# ProDocument___2024-03-31.net
KiCad netlist of a schematic drawn in EasyEDA Pro
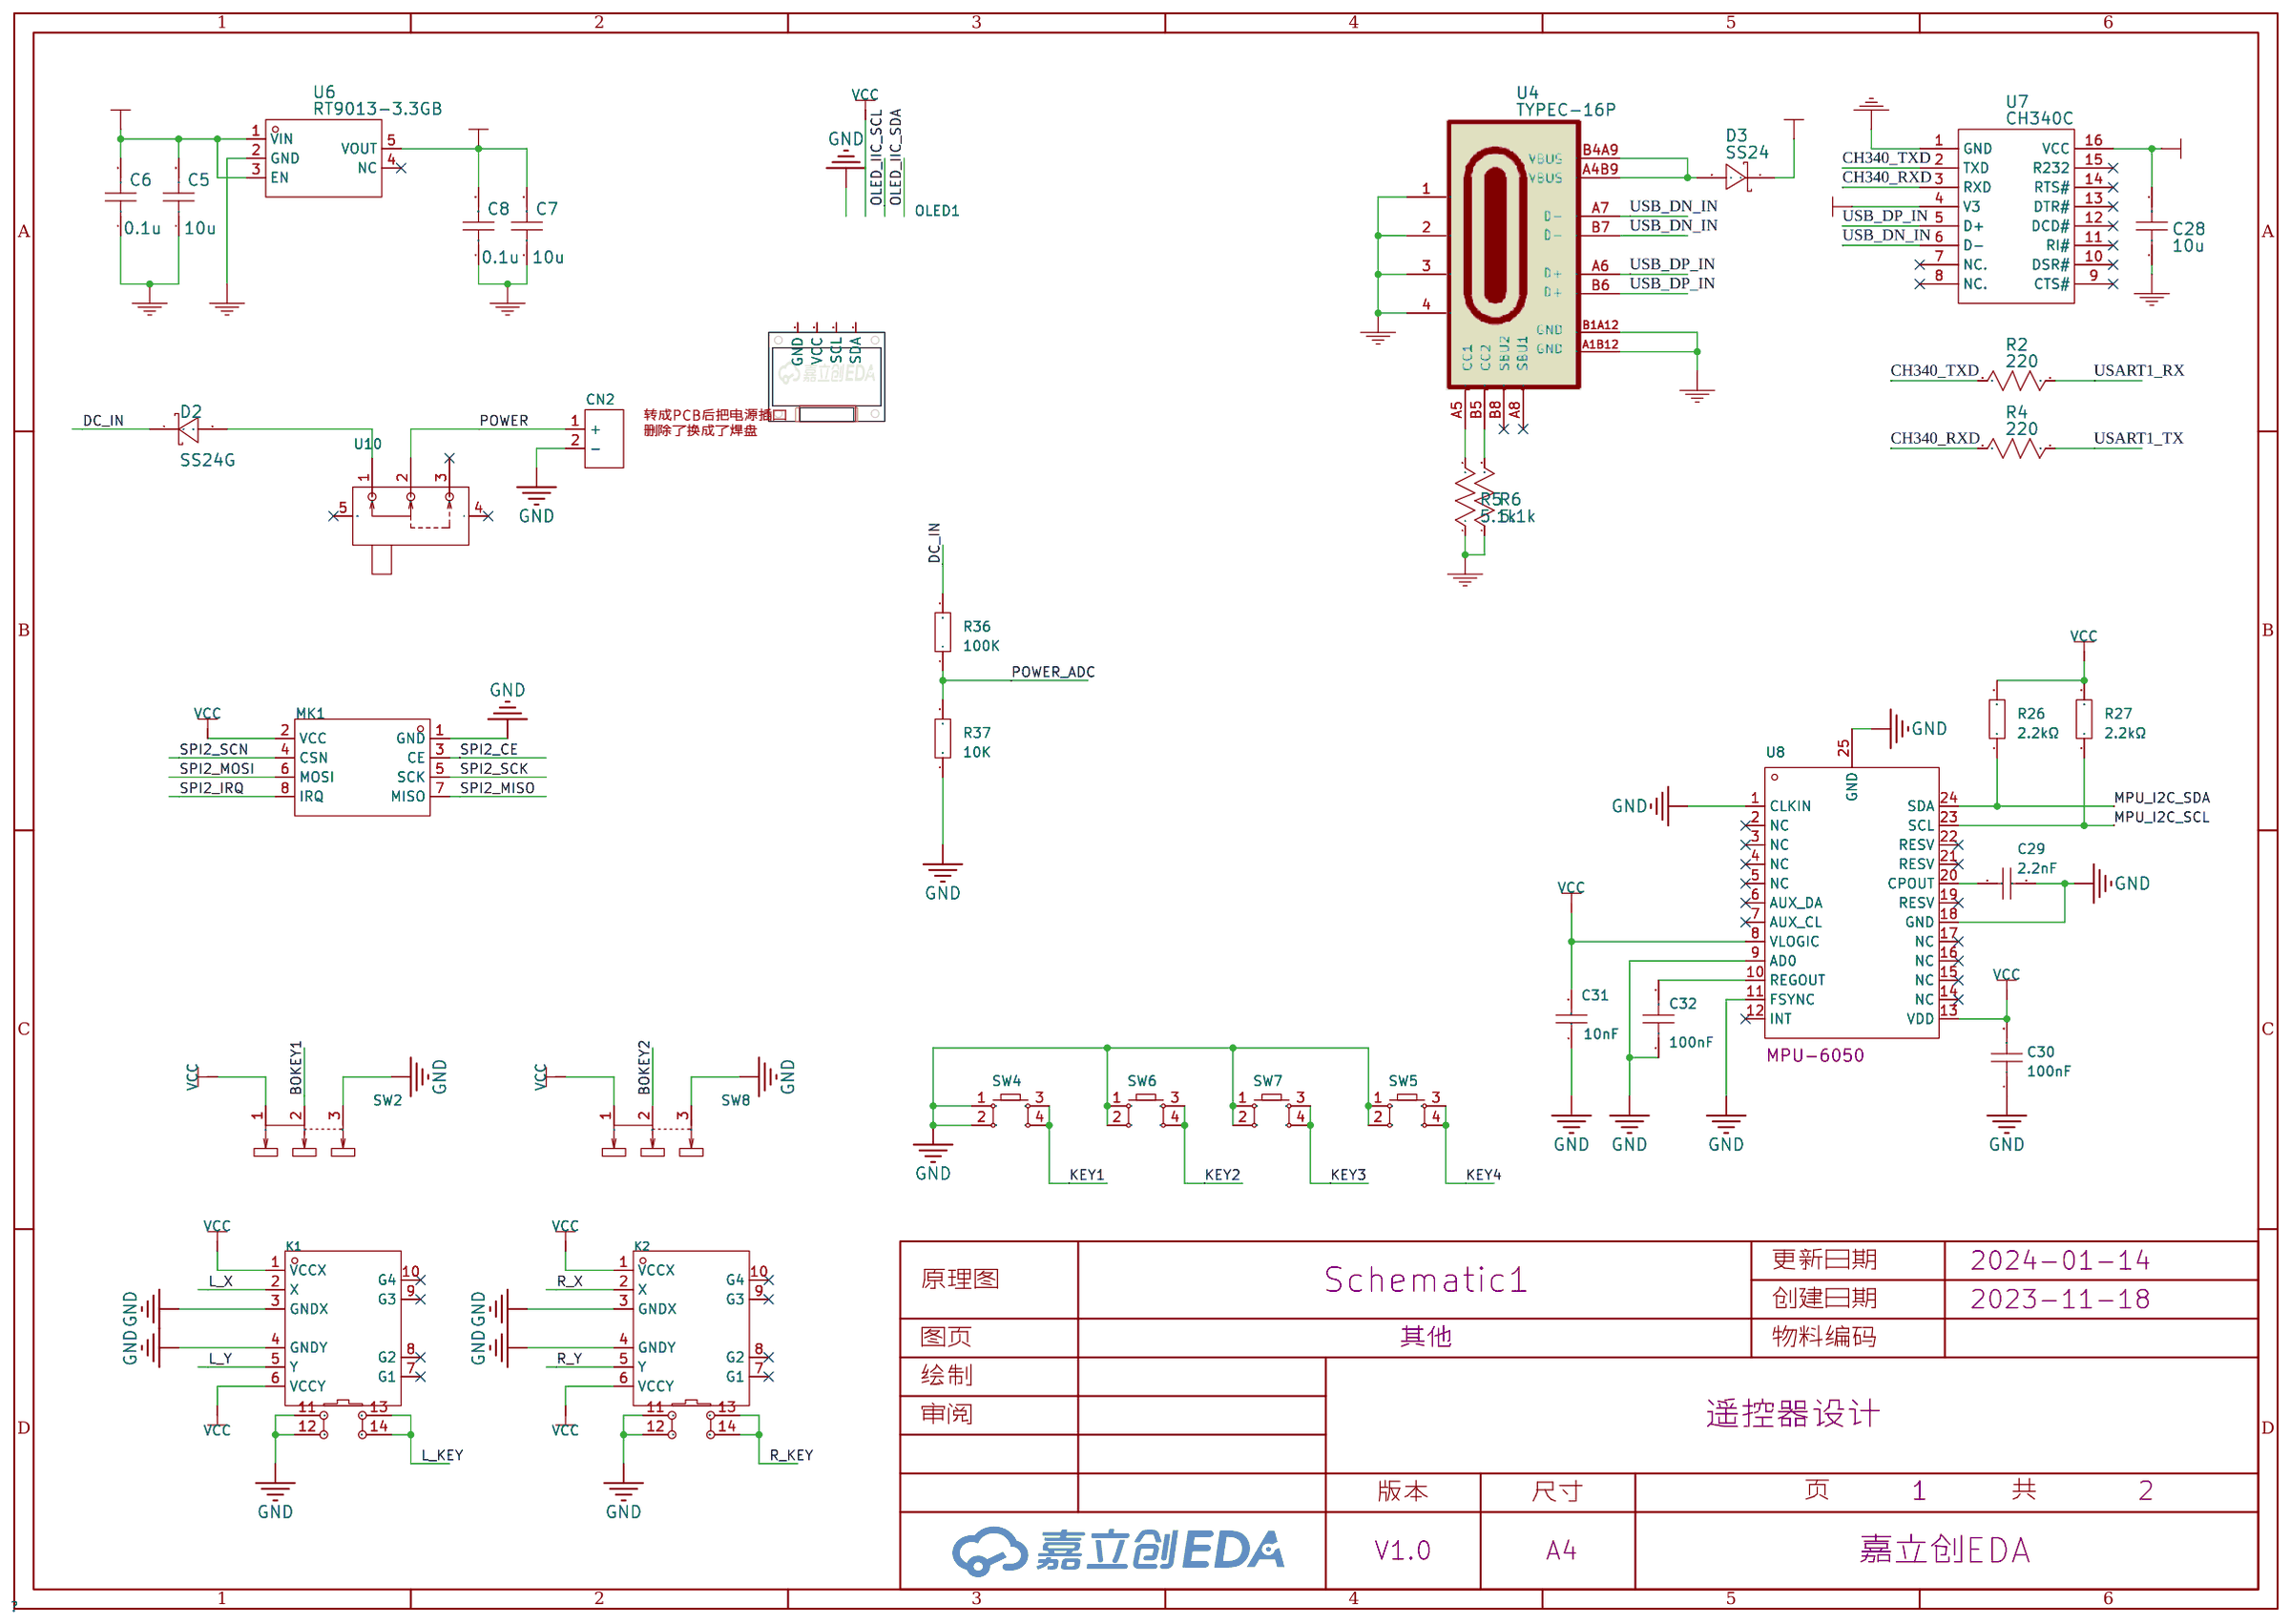
[diagram p0: 其他]
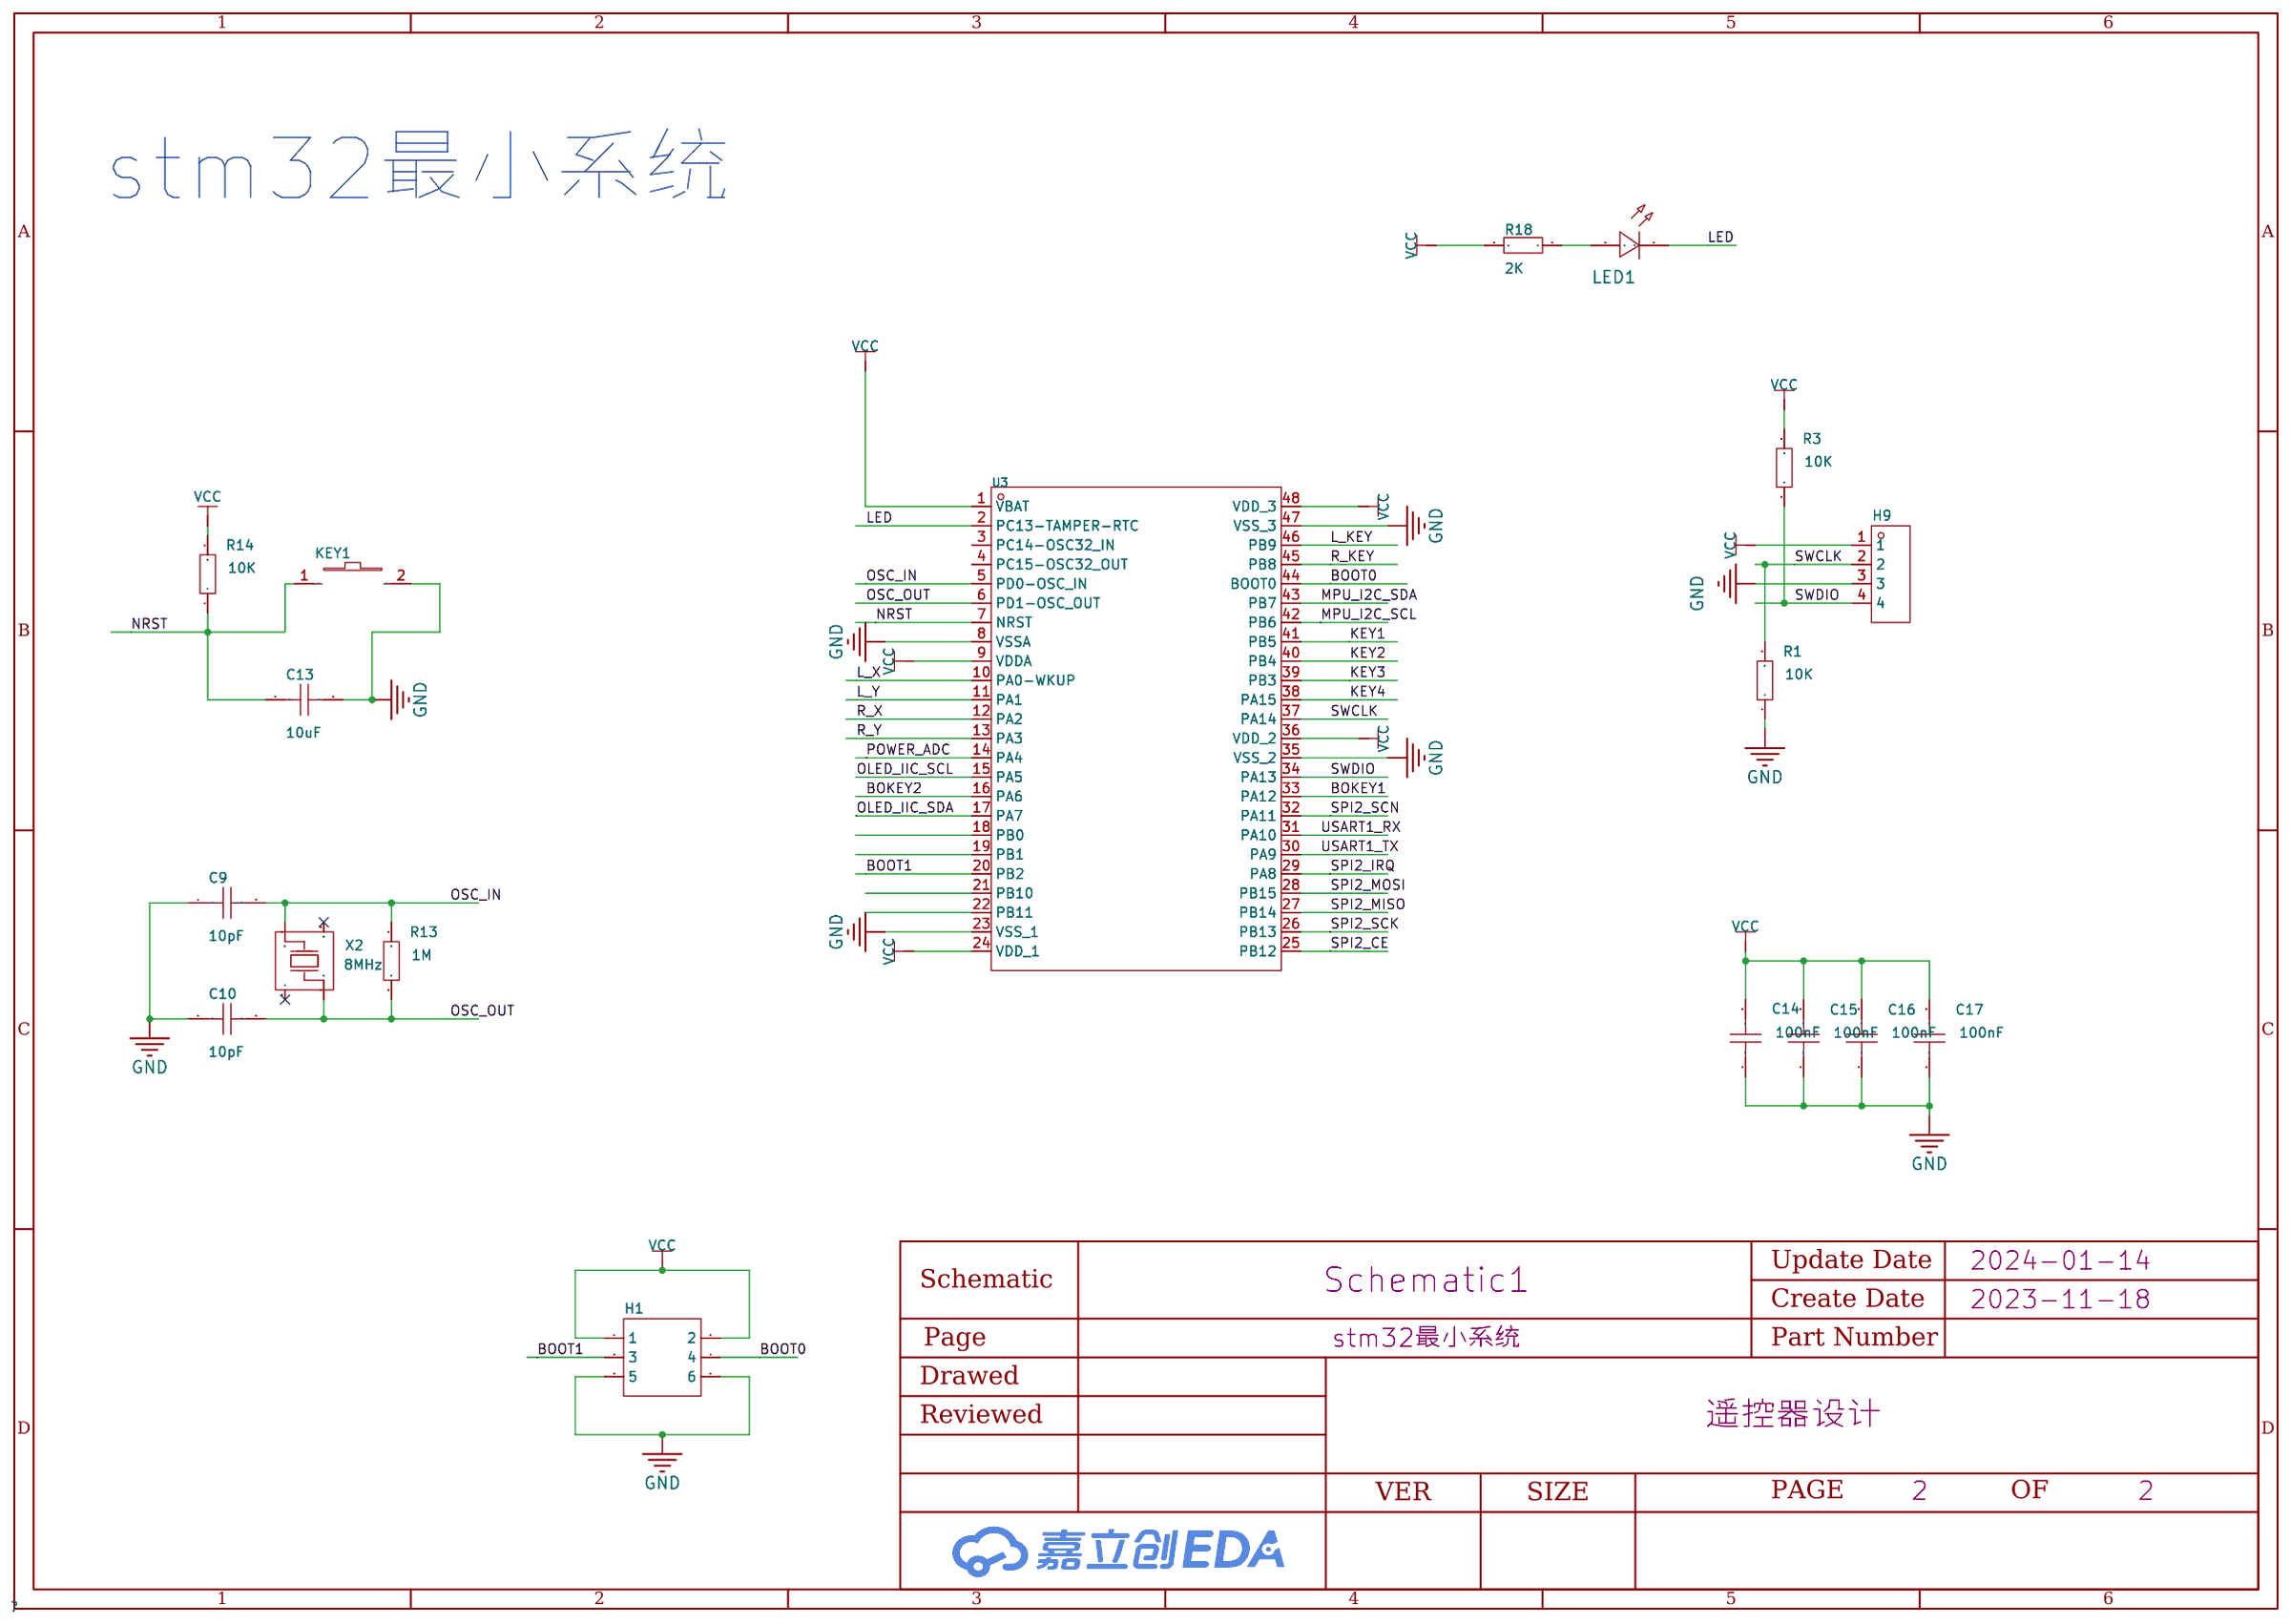
[diagram p1: stm32最小系统]

(export (version "E")
  (design (tool "Eeschema 10.0.6"))
  (components
    (comp (ref "C5") (value "10u") (footprint "easyedapro:C0603") (libsource (lib "easyedapro") (part "10u")))
    (comp (ref "C6")
      (value "0.1u")
      (footprint "easyedapro:C0603")
      (libsource (lib "easyedapro") (part "0.1u"))
    )
    (comp (ref "C7") (value "10u") (footprint "easyedapro:C0603") (libsource (lib "easyedapro") (part "10u")))
    (comp (ref "C8")
      (value "0.1u")
      (footprint "easyedapro:C0603")
      (libsource (lib "easyedapro") (part "0.1u"))
    )
    (comp (ref "C28")
      (value "10u")
      (footprint "easyedapro:C0603")
      (libsource (lib "easyedapro") (part "10u"))
    )
    (comp (ref "C29")
      (value "2.2nF")
      (footprint "easyedapro:C0402")
      (description "容值:2.2nF;精度:±10%;额定电压:50V;材质(温度系数):X7R;")
      (fields (field (name "Manufacturer Part") "0402B222K500NT") (field (name "Manufacturer") "FH(风华)"))
      (libsource (lib "easyedapro") (part "0402B222K500NT"))
    )
    (comp (ref "C30")
      (value "100nF")
      (footprint "easyedapro:C0402")
      (description "容值:100nF;精度:±10%;额定电压:16V;材质(温度系数):X7R;")
      (fields
        (field (name "Manufacturer Part") "CC0402KRX7R7BB104")
        (field (name "Manufacturer") "YAGEO(国巨)")
      )
      (libsource (lib "easyedapro") (part "CC0402KRX7R7BB104"))
    )
    (comp (ref "C31")
      (value "10nF")
      (footprint "easyedapro:C0402")
      (description "容值:10nF;精度:±10%;额定电压:50V;温度系数:X7R;")
      (fields
        (field (name "Manufacturer Part") "CC0402KRX7R9BB103")
        (field (name "Manufacturer") "YAGEO(国巨)")
      )
      (libsource (lib "easyedapro") (part "CC0402KRX7R9BB103"))
    )
    (comp (ref "C32")
      (value "100nF")
      (footprint "easyedapro:C0402")
      (description "容值:100nF;精度:±10%;额定电压:16V;材质(温度系数):X7R;")
      (fields
        (field (name "Manufacturer Part") "CC0402KRX7R7BB104")
        (field (name "Manufacturer") "YAGEO(国巨)")
      )
      (libsource (lib "easyedapro") (part "CC0402KRX7R7BB104"))
    )
    (comp (ref "CN2")
      (value "XT30UPB-F")
      (footprint "easyedapro:CONN-TH_XT30UPB-F")
      (description "模型插头连接器")
      (fields (field (name "Manufacturer") "AMASS(艾迈斯)"))
      (libsource (lib "easyedapro") (part "XT30UPB-F"))
    )
    (comp (ref "D2")
      (value "SS24G")
      (footprint "easyedapro:SMA_L4.4-W2.8-LS5.4-RD")
      (fields (field (name "Manufacturer") "SK"))
      (libsource (lib "easyedapro") (part "SS24G"))
    )
    (comp (ref "D3")
      (value "SS24")
      (footprint "easyedapro:SMA_L4.3-W2.6-LS5.2-RD")
      (fields (field (name "Manufacturer") "MDD"))
      (libsource (lib "easyedapro") (part "SS24"))
    )
    (comp (ref "K1")
      (value "~")
      (footprint "easyedapro:摇杆按键-16x16-直插")
      (libsource (lib "easyedapro") (part "摇杆-按键"))
    )
    (comp (ref "K2")
      (value "~")
      (footprint "easyedapro:摇杆按键-16x16-直插")
      (libsource (lib "easyedapro") (part "摇杆-按键"))
    )
    (comp (ref "MK1")
      (value "NF-04")
      (footprint "easyedapro:WIRELM-SMD_NRF24L01")
      (description "低成本NF-04台产芯片 功率加强版 最佳通讯距离240米，2.4G无线通讯模块")
      (fields (field (name "Manufacturer") "Ai-Thinker(安信可)"))
      (libsource (lib "easyedapro") (part "NRF24L01"))
    )
    (comp (ref "OLED1")
      (value "~")
      (footprint "easyedapro:0.96OLED_4P")
      (libsource (lib "easyedapro") (part "0.96OLED模块_4P"))
    )
    (comp (ref "R2") (value "220") (footprint "easyedapro:R0603") (libsource (lib "easyedapro") (part "220")))
    (comp (ref "R4") (value "220") (footprint "easyedapro:R0603") (libsource (lib "easyedapro") (part "220")))
    (comp (ref "R5")
      (value "5.1k")
      (footprint "easyedapro:R0603")
      (libsource (lib "easyedapro") (part "5.1k"))
    )
    (comp (ref "R6")
      (value "5.1k")
      (footprint "easyedapro:R0603")
      (libsource (lib "easyedapro") (part "5.1k"))
    )
    (comp (ref "R26")
      (value "2.2kΩ")
      (footprint "easyedapro:R0402")
      (description "电阻类型:厚膜电阻;阻值:2.2kΩ;精度:±1%;功率:62.5mW;温度系数:±100ppm/°C;最大工作电压:50V;工作温度范围:-55°C~+155°C;")
      (fields
        (field (name "Manufacturer Part") "0402WGF2201TCE")
        (field (name "Manufacturer") "UNI-ROYAL(厚声)")
      )
      (libsource (lib "easyedapro") (part "0402WGF2201TCE"))
    )
    (comp (ref "R27")
      (value "2.2kΩ")
      (footprint "easyedapro:R0402")
      (description "电阻类型:厚膜电阻;阻值:2.2kΩ;精度:±1%;功率:62.5mW;温度系数:±100ppm/°C;最大工作电压:50V;工作温度范围:-55°C~+155°C;")
      (fields
        (field (name "Manufacturer Part") "0402WGF2201TCE")
        (field (name "Manufacturer") "UNI-ROYAL(厚声)")
      )
      (libsource (lib "easyedapro") (part "0402WGF2201TCE"))
    )
    (comp (ref "R36")
      (value "100K")
      (footprint "easyedapro:R0603")
      (libsource (lib "easyedapro") (part "电阻"))
    )
    (comp (ref "R37") (value "10K") (footprint "easyedapro:R0603") (libsource (lib "easyedapro") (part "电阻")))
    (comp (ref "SW2")
      (value "SS-12D10L5")
      (footprint "easyedapro:SW-TH_SS-12D10L5")
      (description "额定电流(DC):3A;额定电压(DC):125V;额定电流(AC):3A;额定电压(AC):125V;电路结构:单刀双掷;安装方式:直插;机械寿命:1万次;开关颜色:黑色;")
      (fields (field (name "Manufacturer") "XKB Connectivity(中国星坤)"))
      (libsource (lib "easyedapro") (part "SS-12D10L5"))
    )
    (comp (ref "SW4")
      (value "~")
      (footprint "easyedapro:SW-TH_4P-L6.0-W6.0-P4.50-LS6.5")
      (libsource (lib "easyedapro") (part "轻触按键"))
    )
    (comp (ref "SW5")
      (value "~")
      (footprint "easyedapro:SW-TH_4P-L6.0-W6.0-P4.50-LS6.5")
      (libsource (lib "easyedapro") (part "轻触按键"))
    )
    (comp (ref "SW6")
      (value "~")
      (footprint "easyedapro:SW-TH_4P-L6.0-W6.0-P4.50-LS6.5")
      (libsource (lib "easyedapro") (part "轻触按键"))
    )
    (comp (ref "SW7")
      (value "~")
      (footprint "easyedapro:SW-TH_4P-L6.0-W6.0-P4.50-LS6.5")
      (libsource (lib "easyedapro") (part "轻触按键"))
    )
    (comp (ref "SW8")
      (value "SS-12D10L5")
      (footprint "easyedapro:SW-TH_SS-12D10L5")
      (description "额定电流(DC):3A;额定电压(DC):125V;额定电流(AC):3A;额定电压(AC):125V;电路结构:单刀双掷;安装方式:直插;机械寿命:1万次;开关颜色:黑色;")
      (fields (field (name "Manufacturer") "XKB Connectivity(中国星坤)"))
      (libsource (lib "easyedapro") (part "SS-12D10L5"))
    )
    (comp (ref "U4")
      (value "TYPEC-16P")
      (footprint "easyedapro:TYPEC")
      (libsource (lib "easyedapro") (part "TYPEC-16P"))
    )
    (comp (ref "U6")
      (value "RT9013-3.3GB")
      (footprint "easyedapro:SOT-23-5_L2.9-W1.6-P0.94-LS2.8-BL")
      (libsource (lib "easyedapro") (part "RT9013-3.3GB"))
    )
    (comp (ref "U7")
      (value "CH340C")
      (footprint "easyedapro:SOP-16_L10.0-W3.9-P1.27-LS6.0-BL")
      (fields (field (name "Manufacturer") "WCH(南京沁恒)"))
      (libsource (lib "easyedapro") (part "CH340C"))
    )
    (comp (ref "U8")
      (value "~")
      (footprint "easyedapro:QFN-24_L4.0-W4.0-P0.50-BL-EP2.7")
      (description "三轴加速度计和三轴陀螺仪，工作电压：2.375V~3.46V")
      (fields
        (field (name "Manufacturer Part") "MPU-6050")
        (field (name "Manufacturer") "TDK InvenSense(应美盛)")
      )
      (libsource (lib "easyedapro") (part "MPU-6050_C24112"))
    )
    (comp (ref "U10")
      (value "SS-12F23-G4")
      (footprint "easyedapro:SW-TH_SS-12F23-G040")
      (description "电路结构:单刀双掷;安装方式:卧插;开关颜色:黑色;滑钮形状:矩形柱状;引脚样式:PC引脚;开关长度:13mm;开关宽度:5.8mm;开关高度:9mm;")
      (fields (field (name "Manufacturer") "DEALON(德艺隆)"))
      (libsource (lib "easyedapro") (part "SS-12F23-G4"))
    )
    (comp (ref "C9")
      (value "10pF")
      (footprint "easyedapro:C0805")
      (libsource (lib "easyedapro") (part "C1210X7R475K630NT"))
    )
    (comp (ref "C10")
      (value "10pF")
      (footprint "easyedapro:C0805")
      (libsource (lib "easyedapro") (part "C1210X7R475K630NT"))
    )
    (comp (ref "C13")
      (value "10uF")
      (footprint "easyedapro:C0805")
      (fields
        (field (name "Manufacturer Part") "CC0603KRX7R9BB104")
        (field (name "Manufacturer") "YAGEO(国巨)")
        (field (name "Tolerance") "±10%")
      )
      (libsource (lib "easyedapro") (part "C1210X7R475K630NT"))
    )
    (comp (ref "C14")
      (value "100nF")
      (footprint "easyedapro:C0805")
      (libsource (lib "easyedapro") (part "C1210X7R475K630NT"))
    )
    (comp (ref "C15")
      (value "100nF")
      (footprint "easyedapro:C0805")
      (libsource (lib "easyedapro") (part "C1210X7R475K630NT"))
    )
    (comp (ref "C16")
      (value "100nF")
      (footprint "easyedapro:C0805")
      (libsource (lib "easyedapro") (part "C1210X7R475K630NT"))
    )
    (comp (ref "C17")
      (value "100nF")
      (footprint "easyedapro:C0805")
      (libsource (lib "easyedapro") (part "C1210X7R475K630NT"))
    )
    (comp (ref "H1")
      (value "~")
      (footprint "easyedapro:HDR-TH_6P-P2.54-V-F-R2-C3-S2.54")
      (libsource (lib "easyedapro") (part "HDR-F-2.54_2x3"))
    )
    (comp (ref "H9")
      (value "~")
      (footprint "easyedapro:HDR-TH_4P-P2.54-V-M")
      (libsource (lib "easyedapro") (part "PZ254V-11-04P"))
    )
    (comp (ref "KEY1")
      (value "轻触开关3x4x2")
      (footprint "easyedapro:SW-SMD_L4.0-W2.9-LS5.0")
      (description "触点电流:50mA;额定电压(DC):12V;电路结构:单刀单掷;安装方式:立贴;按钮形状:圆形按钮;带灯:-;开关长度:4mm;开关宽度:3mm;开关高度:2mm;")
      (fields (field (name "Manufacturer") "国产"))
      (libsource (lib "easyedapro") (part "Switch3x4x2"))
    )
    (comp (ref "LED1")
      (value "~")
      (footprint "easyedapro:LED0805-RD_RED")
      (libsource (lib "easyedapro") (part "LED_R"))
    )
    (comp (ref "R1") (value "10K") (footprint "easyedapro:R0603") (libsource (lib "easyedapro") (part "电阻")))
    (comp (ref "R3") (value "10K") (footprint "easyedapro:R0603") (libsource (lib "easyedapro") (part "电阻")))
    (comp (ref "R13") (value "1M") (footprint "easyedapro:R0603") (libsource (lib "easyedapro") (part "电阻")))
    (comp (ref "R14") (value "10K") (footprint "easyedapro:R0603") (libsource (lib "easyedapro") (part "电阻")))
    (comp (ref "R18") (value "2K") (footprint "easyedapro:R0603") (libsource (lib "easyedapro") (part "电阻")))
    (comp (ref "U3")
      (value "STM32F103C8T6")
      (footprint "easyedapro:LQFP-48_L7.0-W7.0-P0.50-LS9.0-BL")
      (fields (field (name "Manufacturer") "ST(意法半导体)"))
      (libsource (lib "easyedapro") (part "STM32F103C8T6"))
    )
    (comp (ref "X2")
      (value "8MHz")
      (footprint "easyedapro:OSC-SMD_4P-L3.2-W2.5-BL")
      (description "晶振类型:SMD 谐振器;频率:8MHz;频率公差:±10ppm;频率稳定度:±15ppm;负载电容:10pF;等效串联电阻(ESR):250Ω;工作温度:-;")
      (fields (field (name "Manufacturer Part") "TAXM8M4RDBCCT2T") (field (name "Manufacturer") "TAE(雅晶鑫)"))
      (libsource (lib "easyedapro") (part "TAXM8M4RDBCCT2T"))
    )
  )
  (nets
    (net (code "1") (name "BOKEY1") (class "Default")
      (node (ref "SW2") (pin "2") (pinfunction "2_2") (pintype "input"))
      (node (ref "U3") (pin "33") (pinfunction "PA12_33") (pintype "input"))
    )
    (net (code "2") (name "BOKEY2") (class "Default")
      (node (ref "SW8") (pin "2") (pinfunction "2_2") (pintype "input"))
      (node (ref "U3") (pin "16") (pinfunction "PA6_16") (pintype "input"))
    )
    (net (code "3") (name "BOOT0") (class "Default")
      (node (ref "H1") (pin "4") (pinfunction "4_4") (pintype "input"))
      (node (ref "U3") (pin "44") (pinfunction "BOOT0_44") (pintype "input"))
    )
    (net (code "4") (name "BOOT1") (class "Default")
      (node (ref "H1") (pin "3") (pinfunction "3_3") (pintype "input"))
      (node (ref "U3") (pin "20") (pinfunction "PB2_20") (pintype "input"))
    )
    (net (code "5") (name "CH340_RXD") (class "Default")
      (node (ref "R4") (pin "1") (pinfunction "1_1") (pintype "input"))
      (node (ref "U7") (pin "3") (pinfunction "RXD_3") (pintype "input"))
    )
    (net (code "6") (name "CH340_TXD") (class "Default")
      (node (ref "R2") (pin "1") (pinfunction "1_1") (pintype "input"))
      (node (ref "U7") (pin "2") (pinfunction "TXD_2") (pintype "input"))
    )
    (net (code "7") (name "DC_IN") (class "Default")
      (node (ref "C5") (pin "2") (pinfunction "2_2") (pintype "input"))
      (node (ref "C6") (pin "2") (pinfunction "2_2") (pintype "input"))
      (node (ref "D2") (pin "1") (pinfunction "1_1") (pintype "input"))
      (node (ref "D3") (pin "1") (pinfunction "K_1") (pintype "input"))
      (node (ref "R36") (pin "2") (pinfunction "2_2") (pintype "input"))
      (node (ref "U6") (pin "1") (pinfunction "VIN_1") (pintype "input"))
      (node (ref "U6") (pin "3") (pinfunction "EN_3") (pintype "input"))
    )
    (net (code "8") (name "GND") (class "Default")
      (node (ref "C10") (pin "1") (pinfunction "1_1") (pintype "input"))
      (node (ref "C13") (pin "2") (pinfunction "2_2") (pintype "input"))
      (node (ref "C14") (pin "1") (pinfunction "1_1") (pintype "input"))
      (node (ref "C15") (pin "1") (pinfunction "1_1") (pintype "input"))
      (node (ref "C16") (pin "1") (pinfunction "1_1") (pintype "input"))
      (node (ref "C17") (pin "1") (pinfunction "1_1") (pintype "input"))
      (node (ref "C28") (pin "1") (pinfunction "1_1") (pintype "input"))
      (node (ref "C29") (pin "2") (pinfunction "2_2") (pintype "input"))
      (node (ref "C30") (pin "1") (pinfunction "1_1") (pintype "input"))
      (node (ref "C31") (pin "1") (pinfunction "1_1") (pintype "input"))
      (node (ref "C32") (pin "1") (pinfunction "1_1") (pintype "input"))
      (node (ref "C5") (pin "1") (pinfunction "1_1") (pintype "input"))
      (node (ref "C6") (pin "1") (pinfunction "1_1") (pintype "input"))
      (node (ref "C7") (pin "1") (pinfunction "1_1") (pintype "input"))
      (node (ref "C8") (pin "1") (pinfunction "1_1") (pintype "input"))
      (node (ref "C9") (pin "1") (pinfunction "1_1") (pintype "input"))
      (node (ref "CN2") (pin "2") (pinfunction "-_2") (pintype "input"))
      (node (ref "H1") (pin "5") (pinfunction "5_5") (pintype "input"))
      (node (ref "H1") (pin "6") (pinfunction "6_6") (pintype "input"))
      (node (ref "H9") (pin "3") (pinfunction "3_3") (pintype "input"))
      (node (ref "K1") (pin "11") (pinfunction "10_11") (pintype "input"))
      (node (ref "K1") (pin "12") (pinfunction "11_12") (pintype "input"))
      (node (ref "K1") (pin "3") (pinfunction "GNDX_3") (pintype "input"))
      (node (ref "K1") (pin "4") (pinfunction "GNDY_4") (pintype "input"))
      (node (ref "K2") (pin "11") (pinfunction "10_11") (pintype "input"))
      (node (ref "K2") (pin "12") (pinfunction "11_12") (pintype "input"))
      (node (ref "K2") (pin "3") (pinfunction "GNDX_3") (pintype "input"))
      (node (ref "K2") (pin "4") (pinfunction "GNDY_4") (pintype "input"))
      (node (ref "KEY1") (pin "2") (pinfunction "2_2") (pintype "input"))
      (node (ref "MK1") (pin "1") (pinfunction "GND_1") (pintype "input"))
      (node (ref "R1") (pin "1") (pinfunction "1_1") (pintype "input"))
      (node (ref "R37") (pin "1") (pinfunction "1_1") (pintype "input"))
      (node (ref "R5") (pin "1") (pinfunction "1_1") (pintype "input"))
      (node (ref "R6") (pin "1") (pinfunction "1_1") (pintype "input"))
      (node (ref "SW2") (pin "3") (pinfunction "3_3") (pintype "input"))
      (node (ref "SW4") (pin "1") (pinfunction "1_1") (pintype "input"))
      (node (ref "SW4") (pin "2") (pinfunction "2_2") (pintype "input"))
      (node (ref "SW5") (pin "1") (pinfunction "1_1") (pintype "input"))
      (node (ref "SW5") (pin "2") (pinfunction "2_2") (pintype "input"))
      (node (ref "SW6") (pin "1") (pinfunction "1_1") (pintype "input"))
      (node (ref "SW6") (pin "2") (pinfunction "2_2") (pintype "input"))
      (node (ref "SW7") (pin "1") (pinfunction "1_1") (pintype "input"))
      (node (ref "SW7") (pin "2") (pinfunction "2_2") (pintype "input"))
      (node (ref "SW8") (pin "3") (pinfunction "3_3") (pintype "input"))
      (node (ref "U3") (pin "23") (pinfunction "VSS_1_23") (pintype "input"))
      (node (ref "U3") (pin "35") (pinfunction "VSS_2_35") (pintype "input"))
      (node (ref "U3") (pin "47") (pinfunction "VSS_3_47") (pintype "input"))
      (node (ref "U3") (pin "8") (pinfunction "VSSA_8") (pintype "input"))
      (node (ref "U4") (pin "1") (pinfunction "1_1") (pintype "input"))
      (node (ref "U4") (pin "2") (pinfunction "1_2") (pintype "input"))
      (node (ref "U4") (pin "3") (pinfunction "1_3") (pintype "input"))
      (node (ref "U4") (pin "4") (pinfunction "1_4") (pintype "input"))
      (node (ref "U4") (pin "A1B12") (pinfunction "1_A1B12") (pintype "input"))
      (node (ref "U4") (pin "B1A12") (pinfunction "1_B1A12") (pintype "input"))
      (node (ref "U6") (pin "2") (pinfunction "GND_2") (pintype "input"))
      (node (ref "U7") (pin "1") (pinfunction "GND_1") (pintype "input"))
      (node (ref "U8") (pin "1") (pinfunction "CLKIN_1") (pintype "input"))
      (node (ref "U8") (pin "11") (pinfunction "FSYNC_11") (pintype "input"))
      (node (ref "U8") (pin "18") (pinfunction "GND_18") (pintype "input"))
      (node (ref "U8") (pin "25") (pinfunction "GND_25") (pintype "input"))
      (node (ref "U8") (pin "9") (pinfunction "AD0_9") (pintype "input"))
    )
    (net (code "9") (name "KEY1") (class "Default")
      (node (ref "SW4") (pin "3") (pinfunction "3_3") (pintype "input"))
      (node (ref "SW4") (pin "4") (pinfunction "4_4") (pintype "input"))
      (node (ref "U3") (pin "41") (pinfunction "PB5_41") (pintype "input"))
    )
    (net (code "10") (name "KEY2") (class "Default")
      (node (ref "SW6") (pin "3") (pinfunction "3_3") (pintype "input"))
      (node (ref "SW6") (pin "4") (pinfunction "4_4") (pintype "input"))
      (node (ref "U3") (pin "40") (pinfunction "PB4_40") (pintype "input"))
    )
    (net (code "11") (name "KEY3") (class "Default")
      (node (ref "SW7") (pin "3") (pinfunction "3_3") (pintype "input"))
      (node (ref "SW7") (pin "4") (pinfunction "4_4") (pintype "input"))
      (node (ref "U3") (pin "39") (pinfunction "PB3_39") (pintype "input"))
    )
    (net (code "12") (name "KEY4") (class "Default")
      (node (ref "SW5") (pin "3") (pinfunction "3_3") (pintype "input"))
      (node (ref "SW5") (pin "4") (pinfunction "4_4") (pintype "input"))
      (node (ref "U3") (pin "38") (pinfunction "PA15_38") (pintype "input"))
    )
    (net (code "13") (name "LED") (class "Default")
      (node (ref "LED1") (pin "1") (pinfunction "C_1") (pintype "input"))
      (node (ref "U3") (pin "2") (pinfunction "PC13-TAMPER-RTC_2") (pintype "input"))
    )
    (net (code "14") (name "L_KEY") (class "Default")
      (node (ref "K1") (pin "13") (pinfunction "12_13") (pintype "input"))
      (node (ref "K1") (pin "14") (pinfunction "13_14") (pintype "input"))
      (node (ref "U3") (pin "46") (pinfunction "PB9_46") (pintype "input"))
    )
    (net (code "15") (name "L_X") (class "Default")
      (node (ref "K1") (pin "2") (pinfunction "X_2") (pintype "input"))
      (node (ref "U3") (pin "10") (pinfunction "PA0-WKUP_10") (pintype "input"))
    )
    (net (code "16") (name "L_Y") (class "Default")
      (node (ref "K1") (pin "5") (pinfunction "Y_5") (pintype "input"))
      (node (ref "U3") (pin "11") (pinfunction "PA1_11") (pintype "input"))
    )
    (net (code "17") (name "MPU_I2C_SCL") (class "Default")
      (node (ref "R27") (pin "1") (pinfunction "1_1") (pintype "input"))
      (node (ref "U3") (pin "42") (pinfunction "PB6_42") (pintype "input"))
      (node (ref "U8") (pin "23") (pinfunction "SCL_23") (pintype "input"))
    )
    (net (code "18") (name "MPU_I2C_SDA") (class "Default")
      (node (ref "R26") (pin "1") (pinfunction "1_1") (pintype "input"))
      (node (ref "U3") (pin "43") (pinfunction "PB7_43") (pintype "input"))
      (node (ref "U8") (pin "24") (pinfunction "SDA_24") (pintype "input"))
    )
    (net (code "19") (name "NRST") (class "Default")
      (node (ref "C13") (pin "1") (pinfunction "1_1") (pintype "input"))
      (node (ref "KEY1") (pin "1") (pinfunction "1_1") (pintype "input"))
      (node (ref "R14") (pin "1") (pinfunction "1_1") (pintype "input"))
      (node (ref "U3") (pin "7") (pinfunction "NRST_7") (pintype "input"))
    )
    (net (code "20") (name "Net-(D2-Pad2)") (class "Default")
      (node (ref "D2") (pin "2") (pinfunction "2_2") (pintype "input"))
      (node (ref "U10") (pin "1") (pinfunction "1_1") (pintype "input"))
    )
    (net (code "21") (name "Net-(D3-A)") (class "Default")
      (node (ref "D3") (pin "2") (pinfunction "A_2") (pintype "input"))
      (node (ref "U4") (pin "A4B9") (pinfunction "1_A4B9") (pintype "input"))
      (node (ref "U4") (pin "B4A9") (pinfunction "1_B4A9") (pintype "input"))
    )
    (net (code "22") (name "Net-(LED1-A)") (class "Default")
      (node (ref "LED1") (pin "2") (pinfunction "A_2") (pintype "input"))
      (node (ref "R18") (pin "1") (pinfunction "1_1") (pintype "input"))
    )
    (net (code "23") (name "Net-(R5-Pad2)") (class "Default")
      (node (ref "R5") (pin "2") (pinfunction "2_2") (pintype "input"))
      (node (ref "U4") (pin "A5") (pinfunction "1_A5") (pintype "input"))
    )
    (net (code "24") (name "Net-(R6-Pad2)") (class "Default")
      (node (ref "R6") (pin "2") (pinfunction "2_2") (pintype "input"))
      (node (ref "U4") (pin "B5") (pinfunction "1_B5") (pintype "input"))
    )
    (net (code "25") (name "Net-(U8-CPOUT)") (class "Default")
      (node (ref "C29") (pin "1") (pinfunction "1_1") (pintype "input"))
      (node (ref "U8") (pin "20") (pinfunction "CPOUT_20") (pintype "input"))
    )
    (net (code "26") (name "Net-(U8-REGOUT)") (class "Default")
      (node (ref "C32") (pin "2") (pinfunction "2_2") (pintype "input"))
      (node (ref "U8") (pin "10") (pinfunction "REGOUT_10") (pintype "input"))
    )
    (net (code "27") (name "OLED_IIC_SCL") (class "Default")
      (node (ref "U3") (pin "15") (pinfunction "PA5_15") (pintype "input"))
    )
    (net (code "28") (name "OLED_IIC_SDA") (class "Default")
      (node (ref "U3") (pin "17") (pinfunction "PA7_17") (pintype "input"))
    )
    (net (code "29") (name "OSC_IN") (class "Default")
      (node (ref "C9") (pin "2") (pinfunction "2_2") (pintype "input"))
      (node (ref "R13") (pin "2") (pinfunction "2_2") (pintype "input"))
      (node (ref "U3") (pin "5") (pinfunction "PD0-OSC_IN_5") (pintype "input"))
      (node (ref "X2") (pin "3") (pinfunction "3_3") (pintype "input"))
    )
    (net (code "30") (name "OSC_OUT") (class "Default")
      (node (ref "C10") (pin "2") (pinfunction "2_2") (pintype "input"))
      (node (ref "R13") (pin "1") (pinfunction "1_1") (pintype "input"))
      (node (ref "U3") (pin "6") (pinfunction "PD1-OSC_OUT_6") (pintype "input"))
      (node (ref "X2") (pin "1") (pinfunction "1_1") (pintype "input"))
    )
    (net (code "31") (name "POWER") (class "Default")
      (node (ref "CN2") (pin "1") (pinfunction "+_1") (pintype "input"))
      (node (ref "U10") (pin "2") (pinfunction "2_2") (pintype "input"))
    )
    (net (code "32") (name "POWER_ADC") (class "Default")
      (node (ref "R36") (pin "1") (pinfunction "1_1") (pintype "input"))
      (node (ref "R37") (pin "2") (pinfunction "2_2") (pintype "input"))
      (node (ref "U3") (pin "14") (pinfunction "PA4_14") (pintype "input"))
    )
    (net (code "33") (name "R_KEY") (class "Default")
      (node (ref "K2") (pin "13") (pinfunction "12_13") (pintype "input"))
      (node (ref "K2") (pin "14") (pinfunction "13_14") (pintype "input"))
      (node (ref "U3") (pin "45") (pinfunction "PB8_45") (pintype "input"))
    )
    (net (code "34") (name "R_X") (class "Default")
      (node (ref "K2") (pin "2") (pinfunction "X_2") (pintype "input"))
      (node (ref "U3") (pin "12") (pinfunction "PA2_12") (pintype "input"))
    )
    (net (code "35") (name "R_Y") (class "Default")
      (node (ref "K2") (pin "5") (pinfunction "Y_5") (pintype "input"))
      (node (ref "U3") (pin "13") (pinfunction "PA3_13") (pintype "input"))
    )
    (net (code "36") (name "SPI2_CE") (class "Default")
      (node (ref "MK1") (pin "3") (pinfunction "CE_3") (pintype "input"))
      (node (ref "U3") (pin "25") (pinfunction "PB12_25") (pintype "input"))
    )
    (net (code "37") (name "SPI2_IRQ") (class "Default")
      (node (ref "MK1") (pin "8") (pinfunction "IRQ_8") (pintype "input"))
      (node (ref "U3") (pin "29") (pinfunction "PA8_29") (pintype "input"))
    )
    (net (code "38") (name "SPI2_MISO") (class "Default")
      (node (ref "MK1") (pin "7") (pinfunction "MISO_7") (pintype "input"))
      (node (ref "U3") (pin "27") (pinfunction "PB14_27") (pintype "input"))
    )
    (net (code "39") (name "SPI2_MOSI") (class "Default")
      (node (ref "MK1") (pin "6") (pinfunction "MOSI_6") (pintype "input"))
      (node (ref "U3") (pin "28") (pinfunction "PB15_28") (pintype "input"))
    )
    (net (code "40") (name "SPI2_SCK") (class "Default")
      (node (ref "MK1") (pin "5") (pinfunction "SCK_5") (pintype "input"))
      (node (ref "U3") (pin "26") (pinfunction "PB13_26") (pintype "input"))
    )
    (net (code "41") (name "SPI2_SCN") (class "Default")
      (node (ref "MK1") (pin "4") (pinfunction "CSN_4") (pintype "input"))
      (node (ref "U3") (pin "32") (pinfunction "PA11_32") (pintype "input"))
    )
    (net (code "42") (name "SWCLK") (class "Default")
      (node (ref "H9") (pin "2") (pinfunction "2_2") (pintype "input"))
      (node (ref "R1") (pin "2") (pinfunction "2_2") (pintype "input"))
      (node (ref "U3") (pin "37") (pinfunction "PA14_37") (pintype "input"))
    )
    (net (code "43") (name "SWDIO") (class "Default")
      (node (ref "H9") (pin "4") (pinfunction "4_4") (pintype "input"))
      (node (ref "R3") (pin "1") (pinfunction "1_1") (pintype "input"))
      (node (ref "U3") (pin "34") (pinfunction "PA13_34") (pintype "input"))
    )
    (net (code "44") (name "USART1_RX") (class "Default")
      (node (ref "R2") (pin "2") (pinfunction "2_2") (pintype "input"))
      (node (ref "U3") (pin "31") (pinfunction "PA10_31") (pintype "input"))
    )
    (net (code "45") (name "USART1_TX") (class "Default")
      (node (ref "R4") (pin "2") (pinfunction "2_2") (pintype "input"))
      (node (ref "U3") (pin "30") (pinfunction "PA9_30") (pintype "input"))
    )
    (net (code "46") (name "USB_DN_IN") (class "Default")
      (node (ref "U4") (pin "A7") (pinfunction "1_A7") (pintype "input"))
      (node (ref "U4") (pin "B7") (pinfunction "1_B7") (pintype "input"))
      (node (ref "U7") (pin "6") (pinfunction "D-_6") (pintype "input"))
    )
    (net (code "47") (name "USB_DP_IN") (class "Default")
      (node (ref "U4") (pin "A6") (pinfunction "1_A6") (pintype "input"))
      (node (ref "U4") (pin "B6") (pinfunction "1_B6") (pintype "input"))
      (node (ref "U7") (pin "5") (pinfunction "D+_5") (pintype "input"))
    )
    (net (code "48") (name "VCC") (class "Default")
      (node (ref "C14") (pin "2") (pinfunction "2_2") (pintype "input"))
      (node (ref "C15") (pin "2") (pinfunction "2_2") (pintype "input"))
      (node (ref "C16") (pin "2") (pinfunction "2_2") (pintype "input"))
      (node (ref "C17") (pin "2") (pinfunction "2_2") (pintype "input"))
      (node (ref "C28") (pin "2") (pinfunction "2_2") (pintype "input"))
      (node (ref "C30") (pin "2") (pinfunction "2_2") (pintype "input"))
      (node (ref "C31") (pin "2") (pinfunction "2_2") (pintype "input"))
      (node (ref "C7") (pin "2") (pinfunction "2_2") (pintype "input"))
      (node (ref "C8") (pin "2") (pinfunction "2_2") (pintype "input"))
      (node (ref "H1") (pin "1") (pinfunction "1_1") (pintype "input"))
      (node (ref "H1") (pin "2") (pinfunction "2_2") (pintype "input"))
      (node (ref "H9") (pin "1") (pinfunction "1_1") (pintype "input"))
      (node (ref "K1") (pin "1") (pinfunction "VCCX_1") (pintype "input"))
      (node (ref "K1") (pin "6") (pinfunction "VCCY_6") (pintype "input"))
      (node (ref "K2") (pin "1") (pinfunction "VCCX_1") (pintype "input"))
      (node (ref "K2") (pin "6") (pinfunction "VCCY_6") (pintype "input"))
      (node (ref "MK1") (pin "2") (pinfunction "VCC_2") (pintype "input"))
      (node (ref "R14") (pin "2") (pinfunction "2_2") (pintype "input"))
      (node (ref "R18") (pin "2") (pinfunction "2_2") (pintype "input"))
      (node (ref "R26") (pin "2") (pinfunction "2_2") (pintype "input"))
      (node (ref "R27") (pin "2") (pinfunction "2_2") (pintype "input"))
      (node (ref "R3") (pin "2") (pinfunction "2_2") (pintype "input"))
      (node (ref "SW2") (pin "1") (pinfunction "1_1") (pintype "input"))
      (node (ref "SW8") (pin "1") (pinfunction "1_1") (pintype "input"))
      (node (ref "U3") (pin "1") (pinfunction "VBAT_1") (pintype "input"))
      (node (ref "U3") (pin "24") (pinfunction "VDD_1_24") (pintype "input"))
      (node (ref "U3") (pin "36") (pinfunction "VDD_2_36") (pintype "input"))
      (node (ref "U3") (pin "48") (pinfunction "VDD_3_48") (pintype "input"))
      (node (ref "U3") (pin "9") (pinfunction "VDDA_9") (pintype "input"))
      (node (ref "U6") (pin "5") (pinfunction "VOUT_5") (pintype "input"))
      (node (ref "U7") (pin "16") (pinfunction "VCC_16") (pintype "input"))
      (node (ref "U7") (pin "4") (pinfunction "V3_4") (pintype "input"))
      (node (ref "U8") (pin "13") (pinfunction "VDD_13") (pintype "input"))
      (node (ref "U8") (pin "8") (pinfunction "VLOGIC_8") (pintype "input"))
    )
    (net (code "49") (name "unconnected-(K1-G1-Pad7)") (class "Default")
      (node (ref "K1") (pin "7") (pinfunction "G1_7") (pintype "input+no_connect"))
    )
    (net (code "50") (name "unconnected-(K1-G2-Pad8)") (class "Default")
      (node (ref "K1") (pin "8") (pinfunction "G2_8") (pintype "input+no_connect"))
    )
    (net (code "51") (name "unconnected-(K1-G3-Pad9)") (class "Default")
      (node (ref "K1") (pin "9") (pinfunction "G3_9") (pintype "input+no_connect"))
    )
    (net (code "52") (name "unconnected-(K1-G4-Pad10)") (class "Default")
      (node (ref "K1") (pin "10") (pinfunction "G4_10") (pintype "input+no_connect"))
    )
    (net (code "53") (name "unconnected-(K2-G1-Pad7)") (class "Default")
      (node (ref "K2") (pin "7") (pinfunction "G1_7") (pintype "input+no_connect"))
    )
    (net (code "54") (name "unconnected-(K2-G2-Pad8)") (class "Default")
      (node (ref "K2") (pin "8") (pinfunction "G2_8") (pintype "input+no_connect"))
    )
    (net (code "55") (name "unconnected-(K2-G3-Pad9)") (class "Default")
      (node (ref "K2") (pin "9") (pinfunction "G3_9") (pintype "input+no_connect"))
    )
    (net (code "56") (name "unconnected-(K2-G4-Pad10)") (class "Default")
      (node (ref "K2") (pin "10") (pinfunction "G4_10") (pintype "input+no_connect"))
    )
    (net (code "57") (name "unconnected-(OLED1-GND-Pad1)") (class "Default")
      (node (ref "OLED1") (pin "1") (pinfunction "GND_1") (pintype "input"))
    )
    (net (code "58") (name "unconnected-(OLED1-SCL-Pad3)") (class "Default")
      (node (ref "OLED1") (pin "3") (pinfunction "SCL_3") (pintype "input"))
    )
    (net (code "59") (name "unconnected-(OLED1-SDA-Pad4)") (class "Default")
      (node (ref "OLED1") (pin "4") (pinfunction "SDA_4") (pintype "input"))
    )
    (net (code "60") (name "unconnected-(OLED1-VCC-Pad2)") (class "Default")
      (node (ref "OLED1") (pin "2") (pinfunction "VCC_2") (pintype "input"))
    )
    (net (code "61") (name "unconnected-(U3-PB0-Pad18)") (class "Default")
      (node (ref "U3") (pin "18") (pinfunction "PB0_18") (pintype "input"))
    )
    (net (code "62") (name "unconnected-(U3-PB1-Pad19)") (class "Default")
      (node (ref "U3") (pin "19") (pinfunction "PB1_19") (pintype "input"))
    )
    (net (code "63") (name "unconnected-(U3-PB10-Pad21)") (class "Default")
      (node (ref "U3") (pin "21") (pinfunction "PB10_21") (pintype "input"))
    )
    (net (code "64") (name "unconnected-(U3-PB11-Pad22)") (class "Default")
      (node (ref "U3") (pin "22") (pinfunction "PB11_22") (pintype "input"))
    )
    (net (code "65") (name "unconnected-(U3-PC14-OSC32_IN-Pad3)") (class "Default")
      (node (ref "U3") (pin "3") (pinfunction "PC14-OSC32_IN_3") (pintype "input"))
    )
    (net (code "66") (name "unconnected-(U3-PC15-OSC32_OUT-Pad4)") (class "Default")
      (node (ref "U3") (pin "4") (pinfunction "PC15-OSC32_OUT_4") (pintype "input"))
    )
    (net (code "67") (name "unconnected-(U4-1-PadA8)") (class "Default")
      (node (ref "U4") (pin "A8") (pinfunction "1_A8") (pintype "input+no_connect"))
    )
    (net (code "68") (name "unconnected-(U4-1-PadB8)") (class "Default")
      (node (ref "U4") (pin "B8") (pinfunction "1_B8") (pintype "input+no_connect"))
    )
    (net (code "69") (name "unconnected-(U6-NC-Pad4)") (class "Default")
      (node (ref "U6") (pin "4") (pinfunction "NC_4") (pintype "input+no_connect"))
    )
    (net (code "70") (name "unconnected-(U7-CTS#-Pad9)") (class "Default")
      (node (ref "U7") (pin "9") (pinfunction "CTS#_9") (pintype "input+no_connect"))
    )
    (net (code "71") (name "unconnected-(U7-DCD#-Pad12)") (class "Default")
      (node (ref "U7") (pin "12") (pinfunction "DCD#_12") (pintype "input+no_connect"))
    )
    (net (code "72") (name "unconnected-(U7-DSR#-Pad10)") (class "Default")
      (node (ref "U7") (pin "10") (pinfunction "DSR#_10") (pintype "input+no_connect"))
    )
    (net (code "73") (name "unconnected-(U7-DTR#-Pad13)") (class "Default")
      (node (ref "U7") (pin "13") (pinfunction "DTR#_13") (pintype "input+no_connect"))
    )
    (net (code "74") (name "unconnected-(U7-NC.-Pad7)") (class "Default")
      (node (ref "U7") (pin "7") (pinfunction "NC._7") (pintype "input+no_connect"))
    )
    (net (code "75") (name "unconnected-(U7-NC.-Pad8)") (class "Default")
      (node (ref "U7") (pin "8") (pinfunction "NC._8") (pintype "input+no_connect"))
    )
    (net (code "76") (name "unconnected-(U7-R232-Pad15)") (class "Default")
      (node (ref "U7") (pin "15") (pinfunction "R232_15") (pintype "input+no_connect"))
    )
    (net (code "77") (name "unconnected-(U7-RI#-Pad11)") (class "Default")
      (node (ref "U7") (pin "11") (pinfunction "RI#_11") (pintype "input+no_connect"))
    )
    (net (code "78") (name "unconnected-(U7-RTS#-Pad14)") (class "Default")
      (node (ref "U7") (pin "14") (pinfunction "RTS#_14") (pintype "input+no_connect"))
    )
    (net (code "79") (name "unconnected-(U8-AUX_CL-Pad7)") (class "Default")
      (node (ref "U8") (pin "7") (pinfunction "AUX_CL_7") (pintype "input+no_connect"))
    )
    (net (code "80") (name "unconnected-(U8-AUX_DA-Pad6)") (class "Default")
      (node (ref "U8") (pin "6") (pinfunction "AUX_DA_6") (pintype "input+no_connect"))
    )
    (net (code "81") (name "unconnected-(U8-INT-Pad12)") (class "Default")
      (node (ref "U8") (pin "12") (pinfunction "INT_12") (pintype "input+no_connect"))
    )
    (net (code "82") (name "unconnected-(U8-NC-Pad2)") (class "Default")
      (node (ref "U8") (pin "2") (pinfunction "NC_2") (pintype "input+no_connect"))
    )
    (net (code "83") (name "unconnected-(U8-NC-Pad3)") (class "Default")
      (node (ref "U8") (pin "3") (pinfunction "NC_3") (pintype "input+no_connect"))
    )
    (net (code "84") (name "unconnected-(U8-NC-Pad4)") (class "Default")
      (node (ref "U8") (pin "4") (pinfunction "NC_4") (pintype "input+no_connect"))
    )
    (net (code "85") (name "unconnected-(U8-NC-Pad5)") (class "Default")
      (node (ref "U8") (pin "5") (pinfunction "NC_5") (pintype "input+no_connect"))
    )
    (net (code "86") (name "unconnected-(U8-NC-Pad14)") (class "Default")
      (node (ref "U8") (pin "14") (pinfunction "NC_14") (pintype "input+no_connect"))
    )
    (net (code "87") (name "unconnected-(U8-NC-Pad15)") (class "Default")
      (node (ref "U8") (pin "15") (pinfunction "NC_15") (pintype "input+no_connect"))
    )
    (net (code "88") (name "unconnected-(U8-NC-Pad16)") (class "Default")
      (node (ref "U8") (pin "16") (pinfunction "NC_16") (pintype "input+no_connect"))
    )
    (net (code "89") (name "unconnected-(U8-NC-Pad17)") (class "Default")
      (node (ref "U8") (pin "17") (pinfunction "NC_17") (pintype "input+no_connect"))
    )
    (net (code "90") (name "unconnected-(U8-RESV-Pad19)") (class "Default")
      (node (ref "U8") (pin "19") (pinfunction "RESV_19") (pintype "input+no_connect"))
    )
    (net (code "91") (name "unconnected-(U8-RESV-Pad21)") (class "Default")
      (node (ref "U8") (pin "21") (pinfunction "RESV_21") (pintype "input+no_connect"))
    )
    (net (code "92") (name "unconnected-(U8-RESV-Pad22)") (class "Default")
      (node (ref "U8") (pin "22") (pinfunction "RESV_22") (pintype "input+no_connect"))
    )
    (net (code "93") (name "unconnected-(U10-Pad3)") (class "Default")
      (node (ref "U10") (pin "3") (pinfunction "3_3") (pintype "input+no_connect"))
    )
    (net (code "94") (name "unconnected-(U10-Pad4)") (class "Default")
      (node (ref "U10") (pin "4") (pinfunction "4_4") (pintype "input+no_connect"))
    )
    (net (code "95") (name "unconnected-(U10-Pad5)") (class "Default")
      (node (ref "U10") (pin "5") (pinfunction "5_5") (pintype "input+no_connect"))
    )
    (net (code "96") (name "unconnected-(X2-Pad2)") (class "Default")
      (node (ref "X2") (pin "2") (pinfunction "2_2") (pintype "input+no_connect"))
    )
    (net (code "97") (name "unconnected-(X2-Pad4)") (class "Default")
      (node (ref "X2") (pin "4") (pinfunction "4_4") (pintype "input+no_connect"))
    )
  )
)
